# QSTL_LED_PCB.net
KiCad netlist of a schematic drawn in Altium Designer
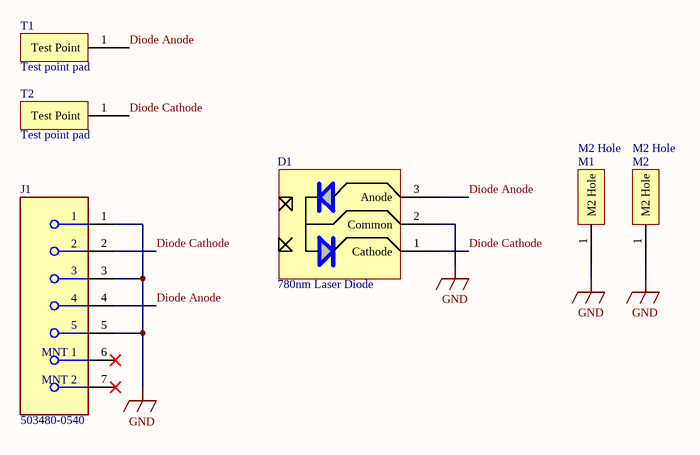
[diagram p0: QSTL_LED_PCB.SchDoc]

(export (version "E")
  (design (tool "Eeschema 10.0.6"))
  (components
    (comp (ref "D1")
      (value "780nm Laser Diode")
      (footprint "D7805I")
      (libsource (lib "QSTL_LED_PCB") (part "D7805I"))
    )
    (comp (ref "J1")
      (value "503480-0540")
      (footprint "FP-503480-0540-MFG")
      (description "503480-0540 Connector FFC/FPC SKT 5 Position 0.5mm Solder Right Angle Surface Mount T/R")
      (libsource (lib "Altium Content Vault") (part "6b037d2877ced340e1c65ac82253790"))
    )
    (comp (ref "M1") (value "M2 Hole") (footprint "M2") (libsource (lib "QSTL_LED_PCB") (part "M2")))
    (comp (ref "M2") (value "M2 Hole") (footprint "M2") (libsource (lib "QSTL_LED_PCB") (part "M2")))
    (comp (ref "T1")
      (value "Test point pad")
      (footprint "Test_Point_Pin")
      (libsource (lib "QSTL_LED_PCB") (part "Test_Point_Pin"))
    )
    (comp (ref "T2")
      (value "Test point pad")
      (footprint "Test_Point_Pin")
      (libsource (lib "QSTL_LED_PCB") (part "Test_Point_Pin"))
    )
  )
  (nets
    (net (code "1") (name "/Diode Anode") (class "Default")
      (node (ref "D1") (pin "3") (pinfunction "Anode_3") (pintype "passive"))
      (node (ref "J1") (pin "4") (pinfunction "4_4") (pintype "passive"))
      (node (ref "T1") (pin "1") (pinfunction "Test_Point_1") (pintype "passive"))
    )
    (net (code "2") (name "/Diode Cathode") (class "Default")
      (node (ref "D1") (pin "1") (pinfunction "Cathode_1") (pintype "passive"))
      (node (ref "J1") (pin "2") (pinfunction "2_2") (pintype "passive"))
      (node (ref "T2") (pin "1") (pinfunction "Test_Point_1") (pintype "passive"))
    )
    (net (code "3") (name "GND") (class "Default")
      (node (ref "D1") (pin "2") (pinfunction "Common_2") (pintype "passive"))
      (node (ref "J1") (pin "1") (pinfunction "1_1") (pintype "passive"))
      (node (ref "J1") (pin "3") (pinfunction "3_3") (pintype "passive"))
      (node (ref "J1") (pin "5") (pinfunction "5_5") (pintype "passive"))
      (node (ref "M1") (pin "1") (pinfunction "M2_Hole_1") (pintype "passive"))
      (node (ref "M2") (pin "1") (pinfunction "M2_Hole_1") (pintype "passive"))
    )
    (net (code "4") (name "unconnected-(J1-MNT_1-Pad6)") (class "Default")
      (node (ref "J1") (pin "6") (pinfunction "MNT_1_6") (pintype "passive+no_connect"))
    )
    (net (code "5") (name "unconnected-(J1-MNT_2-Pad7)") (class "Default")
      (node (ref "J1") (pin "7") (pinfunction "MNT_2_7") (pintype "passive+no_connect"))
    )
  )
)
